# UART.net
KiCad netlist of a schematic drawn in Altium Designer
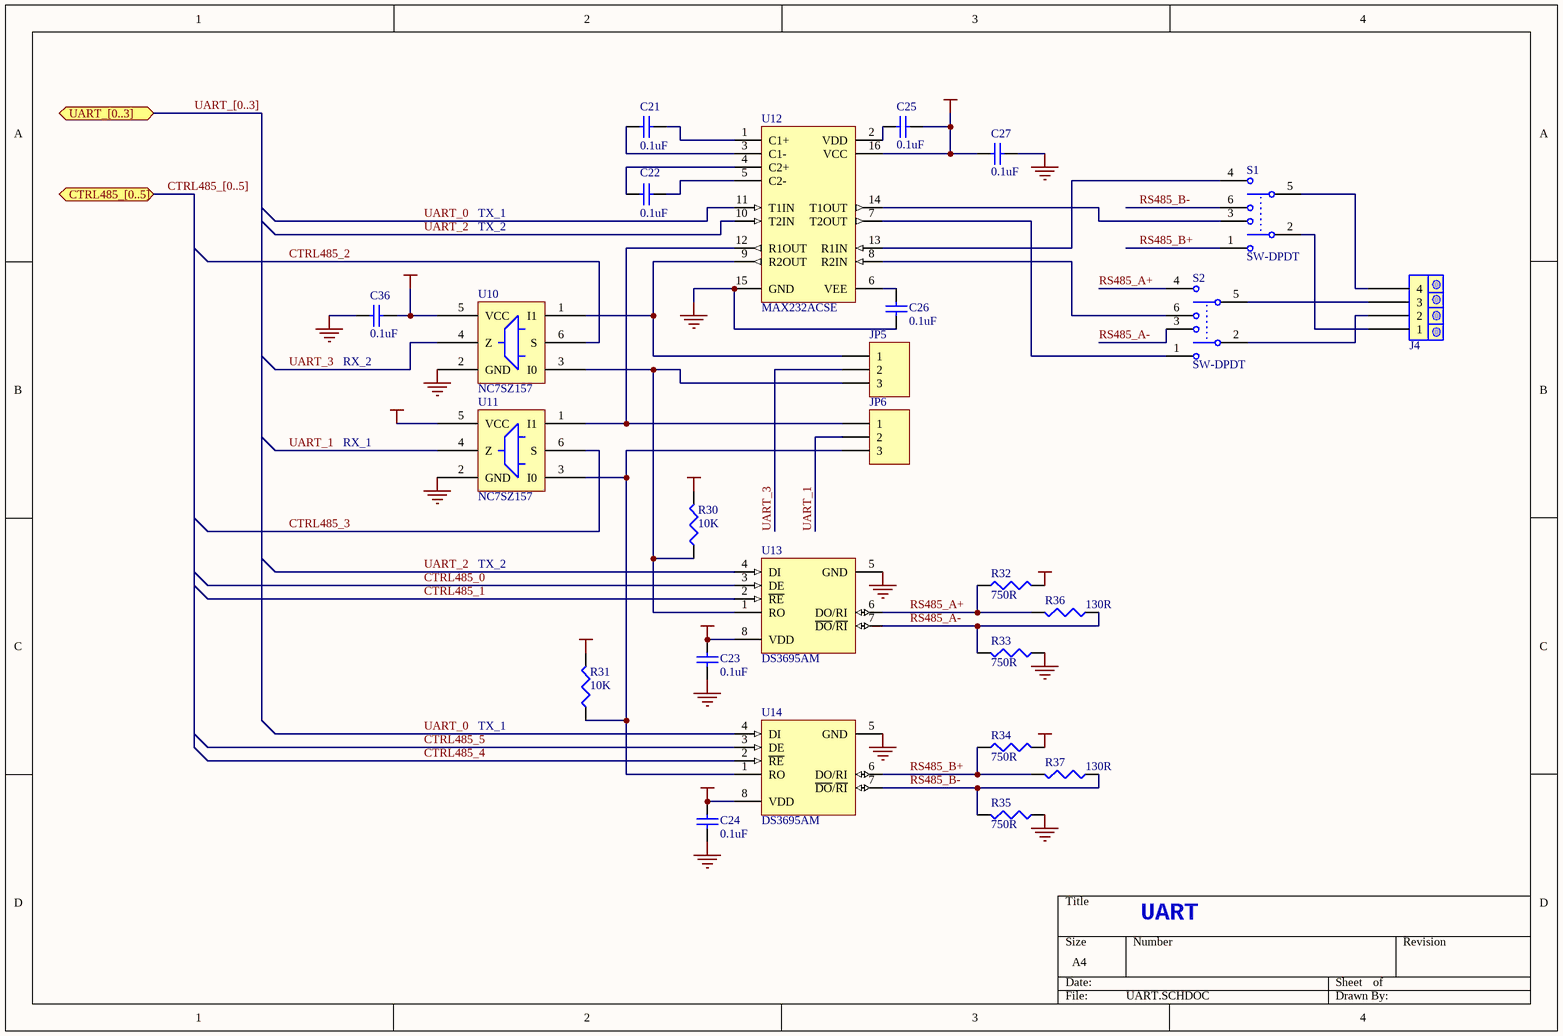
[diagram p0: UART.SCHDOC]

(export (version "E")
  (design (tool "Eeschema 10.0.6"))
  (components
    (comp (ref "C21")
      (value "0.1uF")
      (footprint "_0805")
      (description "Capacitor (Semiconductor SIM Model)")
      (fields (field (name "Comment") "Cap Semi") (field (name "PUBLISHER") "Altium Limited"))
      (libsource (lib "Miscellaneous Devices") (part "Cap Semi"))
    )
    (comp (ref "C22")
      (value "0.1uF")
      (footprint "_0805")
      (description "Capacitor (Semiconductor SIM Model)")
      (fields (field (name "Comment") "Cap Semi") (field (name "PUBLISHER") "Altium Limited"))
      (libsource (lib "Miscellaneous Devices") (part "Cap Semi"))
    )
    (comp (ref "C23")
      (value "0.1uF")
      (footprint "_0805")
      (description "Capacitor (Semiconductor SIM Model)")
      (fields (field (name "Comment") "Cap Semi") (field (name "PUBLISHER") "Altium Limited"))
      (libsource (lib "Miscellaneous Devices") (part "Cap Semi"))
    )
    (comp (ref "C24")
      (value "0.1uF")
      (footprint "_0805")
      (description "Capacitor (Semiconductor SIM Model)")
      (fields (field (name "Comment") "Cap Semi") (field (name "PUBLISHER") "Altium Limited"))
      (libsource (lib "Miscellaneous Devices") (part "Cap Semi"))
    )
    (comp (ref "C25")
      (value "0.1uF")
      (footprint "_0805")
      (description "Capacitor (Semiconductor SIM Model)")
      (fields (field (name "Comment") "Cap Semi") (field (name "PUBLISHER") "Altium Limited"))
      (libsource (lib "Miscellaneous Devices") (part "Cap Semi"))
    )
    (comp (ref "C26")
      (value "0.1uF")
      (footprint "_0805")
      (description "Capacitor (Semiconductor SIM Model)")
      (fields (field (name "Comment") "Cap Semi") (field (name "PUBLISHER") "Altium Limited"))
      (libsource (lib "Miscellaneous Devices") (part "Cap Semi"))
    )
    (comp (ref "C27")
      (value "0.1uF")
      (footprint "_0805")
      (description "Capacitor (Semiconductor SIM Model)")
      (fields (field (name "Comment") "Cap Semi") (field (name "PUBLISHER") "Altium Limited"))
      (libsource (lib "Miscellaneous Devices") (part "Cap Semi"))
    )
    (comp (ref "C36")
      (value "0.1uF")
      (footprint "_0805")
      (description "Capacitor (Semiconductor SIM Model)")
      (fields (field (name "Comment") "Cap Semi") (field (name "PUBLISHER") "Altium Limited"))
      (libsource (lib "Miscellaneous Devices") (part "Cap Semi"))
    )
    (comp (ref "J4")
      (value "BORNERA_X4")
      (footprint "BORNERA_X4")
      (libsource (lib "Custom") (part "BORNERA_X4"))
    )
    (comp (ref "JP5")
      (value "Header 3")
      (footprint "HDR1X3")
      (description "Header, 3-Pin")
      (fields (field (name "PUBLISHER") "Altium Limited"))
      (libsource (lib "Miscellaneous Connectors") (part "Header 3"))
    )
    (comp (ref "JP6")
      (value "Header 3")
      (footprint "HDR1X3")
      (description "Header, 3-Pin")
      (fields (field (name "PUBLISHER") "Altium Limited"))
      (libsource (lib "Miscellaneous Connectors") (part "Header 3"))
    )
    (comp (ref "R30")
      (value "10K")
      (footprint "_0805")
      (description "Resistor")
      (fields (field (name "Comment") "Res3") (field (name "PUBLISHER") "Altium Limited"))
      (libsource (lib "Miscellaneous Devices") (part "Res3"))
    )
    (comp (ref "R31")
      (value "10K")
      (footprint "_0805")
      (description "Resistor")
      (fields (field (name "Comment") "Res3") (field (name "PUBLISHER") "Altium Limited"))
      (libsource (lib "Miscellaneous Devices") (part "Res3"))
    )
    (comp (ref "R32")
      (value "750R")
      (footprint "_1206")
      (description "Resistor")
      (fields (field (name "Comment") "Res3") (field (name "PUBLISHER") "Altium Limited"))
      (libsource (lib "Miscellaneous Devices") (part "Res3"))
    )
    (comp (ref "R33")
      (value "750R")
      (footprint "_1206")
      (description "Resistor")
      (fields (field (name "Comment") "Res3") (field (name "PUBLISHER") "Altium Limited"))
      (libsource (lib "Miscellaneous Devices") (part "Res3"))
    )
    (comp (ref "R34")
      (value "750R")
      (footprint "_1206")
      (description "Resistor")
      (fields (field (name "Comment") "Res3") (field (name "PUBLISHER") "Altium Limited"))
      (libsource (lib "Miscellaneous Devices") (part "Res3"))
    )
    (comp (ref "R35")
      (value "750R")
      (footprint "_1206")
      (description "Resistor")
      (fields (field (name "Comment") "Res3") (field (name "PUBLISHER") "Altium Limited"))
      (libsource (lib "Miscellaneous Devices") (part "Res3"))
    )
    (comp (ref "R36")
      (value "130R")
      (footprint "_1206")
      (description "Resistor")
      (fields (field (name "Comment") "Res3") (field (name "PUBLISHER") "Altium Limited"))
      (libsource (lib "Miscellaneous Devices") (part "Res3"))
    )
    (comp (ref "R37")
      (value "130R")
      (footprint "_1206")
      (description "Resistor")
      (fields (field (name "Comment") "Res3") (field (name "PUBLISHER") "Altium Limited"))
      (libsource (lib "Miscellaneous Devices") (part "Res3"))
    )
    (comp (ref "S1")
      (value "SW-DPDT")
      (footprint "Switch_EG2207")
      (description "Double-Pole, Double-Throw Switch")
      (fields (field (name "PUBLISHER") "Altium Limited"))
      (libsource (lib "Miscellaneous Devices") (part "SW-DPDT"))
    )
    (comp (ref "S2")
      (value "SW-DPDT")
      (footprint "Switch_EG2207")
      (description "Double-Pole, Double-Throw Switch")
      (fields (field (name "PUBLISHER") "Altium Limited"))
      (libsource (lib "Miscellaneous Devices") (part "SW-DPDT"))
    )
    (comp (ref "U10")
      (value "NC7SZ157")
      (footprint "SO-G6/Z2.8")
      (description "Tiny Logic 2-Input Non-Inverter Mux")
      (libsource (lib "Custom") (part "NC7SZ157"))
    )
    (comp (ref "U11")
      (value "NC7SZ157")
      (footprint "SO-G6/Z2.8")
      (description "Tiny Logic 2-Input Non-Inverter Mux")
      (libsource (lib "Custom") (part "NC7SZ157"))
    )
    (comp (ref "U12")
      (value "MAX232ACSE")
      (footprint "NSO16")
      (description "+5V Powered, Multi-Channel RS-232 Driver/Receiver")
      (fields (field (name "PUBLISHER") "Altium Limited"))
      (libsource (lib "Maxim Communication Transceiver") (part "MAX232ACSE"))
    )
    (comp (ref "U13")
      (value "DS3695AM")
      (footprint "M08A")
      (description "Multipoint RS485/RS422 Transceiver")
      (fields (field (name "PUBLISHER") "Altium Limited"))
      (libsource (lib "NSC Interface Line Transceiver") (part "DS3695AM"))
    )
    (comp (ref "U14")
      (value "DS3695AM")
      (footprint "M08A")
      (description "Multipoint RS485/RS422 Transceiver")
      (fields (field (name "PUBLISHER") "Altium Limited"))
      (libsource (lib "NSC Interface Line Transceiver") (part "DS3695AM"))
    )
  )
  (nets
    (net (code "1") (name "/CTRL485_0") (class "Default")
      (node (ref "U13") (pin "3") (pinfunction "DE_3") (pintype "input"))
    )
    (net (code "2") (name "/CTRL485_1") (class "Default")
      (node (ref "U13") (pin "2") (pinfunction "~{RE}_2") (pintype "input"))
    )
    (net (code "3") (name "/CTRL485_2") (class "Default")
      (node (ref "U10") (pin "6") (pinfunction "S_6") (pintype "passive"))
    )
    (net (code "4") (name "/CTRL485_3") (class "Default")
      (node (ref "U11") (pin "6") (pinfunction "S_6") (pintype "passive"))
    )
    (net (code "5") (name "/CTRL485_4") (class "Default")
      (node (ref "U14") (pin "2") (pinfunction "~{RE}_2") (pintype "input"))
    )
    (net (code "6") (name "/CTRL485_5") (class "Default")
      (node (ref "U14") (pin "3") (pinfunction "DE_3") (pintype "input"))
    )
    (net (code "8") (name "/RS485_A+") (class "Default")
      (node (ref "R32") (pin "1") (pinfunction "1_1") (pintype "passive"))
      (node (ref "R36") (pin "2") (pinfunction "2_2") (pintype "passive"))
      (node (ref "S2") (pin "4") (pinfunction "6_4") (pintype "passive"))
      (node (ref "U13") (pin "6") (pinfunction "DO/RI_6") (pintype "bidirectional"))
    )
    (net (code "9") (name "/RS485_A-") (class "Default")
      (node (ref "R33") (pin "2") (pinfunction "2_2") (pintype "passive"))
      (node (ref "R36") (pin "1") (pinfunction "1_1") (pintype "passive"))
      (node (ref "S2") (pin "3") (pinfunction "3_3") (pintype "passive"))
      (node (ref "U13") (pin "7") (pinfunction "~{DO}/~{RI}_7") (pintype "bidirectional"))
    )
    (net (code "10") (name "/RS485_B+") (class "Default")
      (node (ref "R34") (pin "1") (pinfunction "1_1") (pintype "passive"))
      (node (ref "R37") (pin "2") (pinfunction "2_2") (pintype "passive"))
      (node (ref "S1") (pin "1") (pinfunction "2_1") (pintype "passive"))
      (node (ref "U14") (pin "6") (pinfunction "DO/RI_6") (pintype "bidirectional"))
    )
    (net (code "11") (name "/RS485_B-") (class "Default")
      (node (ref "R35") (pin "2") (pinfunction "2_2") (pintype "passive"))
      (node (ref "R37") (pin "1") (pinfunction "1_1") (pintype "passive"))
      (node (ref "S1") (pin "6") (pinfunction "5_6") (pintype "passive"))
      (node (ref "U14") (pin "7") (pinfunction "~{DO}/~{RI}_7") (pintype "bidirectional"))
    )
    (net (code "12") (name "/UART_0") (class "Default")
      (node (ref "U12") (pin "11") (pinfunction "T1IN_11") (pintype "input"))
      (node (ref "U14") (pin "4") (pinfunction "DI_4") (pintype "input"))
    )
    (net (code "13") (name "/UART_1") (class "Default")
      (node (ref "JP6") (pin "2") (pinfunction "2_2") (pintype "passive"))
      (node (ref "U11") (pin "4") (pinfunction "Z_4") (pintype "passive"))
    )
    (net (code "14") (name "/UART_2") (class "Default")
      (node (ref "U12") (pin "10") (pinfunction "T2IN_10") (pintype "input"))
      (node (ref "U13") (pin "4") (pinfunction "DI_4") (pintype "input"))
    )
    (net (code "15") (name "/UART_3") (class "Default")
      (node (ref "JP5") (pin "2") (pinfunction "2_2") (pintype "passive"))
      (node (ref "U10") (pin "4") (pinfunction "Z_4") (pintype "passive"))
    )
    (net (code "17") (name "GND") (class "Default")
      (node (ref "C23") (pin "2") (pinfunction "2_2") (pintype "passive"))
      (node (ref "C24") (pin "2") (pinfunction "2_2") (pintype "passive"))
      (node (ref "C26") (pin "2") (pinfunction "2_2") (pintype "passive"))
      (node (ref "C27") (pin "2") (pinfunction "2_2") (pintype "passive"))
      (node (ref "C36") (pin "1") (pinfunction "1_1") (pintype "passive"))
      (node (ref "R33") (pin "1") (pinfunction "1_1") (pintype "passive"))
      (node (ref "R35") (pin "1") (pinfunction "1_1") (pintype "passive"))
      (node (ref "U10") (pin "2") (pinfunction "GND_2") (pintype "power_in"))
      (node (ref "U11") (pin "2") (pinfunction "GND_2") (pintype "power_in"))
      (node (ref "U12") (pin "15") (pinfunction "GND_15") (pintype "power_in"))
      (node (ref "U13") (pin "5") (pinfunction "GND_5") (pintype "power_in"))
      (node (ref "U14") (pin "5") (pinfunction "GND_5") (pintype "power_in"))
    )
    (net (code "18") (name "Net-(S1-1)") (class "Default")
      (node (ref "J4") (pin "1") (pinfunction "1_1") (pintype "passive"))
      (node (ref "S1") (pin "2") (pinfunction "1_2") (pintype "passive"))
    )
    (net (code "19") (name "Net-(S1-4)") (class "Default")
      (node (ref "J4") (pin "4") (pinfunction "4_4") (pintype "passive"))
      (node (ref "S1") (pin "5") (pinfunction "4_5") (pintype "passive"))
    )
    (net (code "20") (name "Net-(S1-6)") (class "Default")
      (node (ref "S1") (pin "4") (pinfunction "6_4") (pintype "passive"))
      (node (ref "U12") (pin "13") (pinfunction "R1IN_13") (pintype "input"))
    )
    (net (code "21") (name "Net-(S2-1)") (class "Default")
      (node (ref "J4") (pin "2") (pinfunction "2_2") (pintype "passive"))
      (node (ref "S2") (pin "2") (pinfunction "1_2") (pintype "passive"))
    )
    (net (code "22") (name "Net-(S2-2)") (class "Default")
      (node (ref "S2") (pin "1") (pinfunction "2_1") (pintype "passive"))
      (node (ref "U12") (pin "7") (pinfunction "T2OUT_7") (pintype "output"))
    )
    (net (code "23") (name "Net-(S2-4)") (class "Default")
      (node (ref "J4") (pin "3") (pinfunction "3_3") (pintype "passive"))
      (node (ref "S2") (pin "5") (pinfunction "4_5") (pintype "passive"))
    )
    (net (code "24") (name "Net-(S2-5)") (class "Default")
      (node (ref "S2") (pin "6") (pinfunction "5_6") (pintype "passive"))
      (node (ref "U12") (pin "8") (pinfunction "R2IN_8") (pintype "input"))
    )
    (net (code "25") (name "Net-(U10-I0)") (class "Default")
      (node (ref "JP5") (pin "3") (pinfunction "3_3") (pintype "passive"))
      (node (ref "R30") (pin "1") (pinfunction "1_1") (pintype "passive"))
      (node (ref "U10") (pin "3") (pinfunction "I0_3") (pintype "passive"))
      (node (ref "U13") (pin "1") (pinfunction "RO_1") (pintype "tri_state"))
    )
    (net (code "26") (name "Net-(U10-I1)") (class "Default")
      (node (ref "JP5") (pin "1") (pinfunction "1_1") (pintype "passive"))
      (node (ref "U10") (pin "1") (pinfunction "I1_1") (pintype "passive"))
      (node (ref "U12") (pin "9") (pinfunction "R2OUT_9") (pintype "output"))
    )
    (net (code "27") (name "Net-(U11-I0)") (class "Default")
      (node (ref "JP6") (pin "3") (pinfunction "3_3") (pintype "passive"))
      (node (ref "R31") (pin "1") (pinfunction "1_1") (pintype "passive"))
      (node (ref "U11") (pin "3") (pinfunction "I0_3") (pintype "passive"))
      (node (ref "U14") (pin "1") (pinfunction "RO_1") (pintype "tri_state"))
    )
    (net (code "28") (name "Net-(U11-I1)") (class "Default")
      (node (ref "JP6") (pin "1") (pinfunction "1_1") (pintype "passive"))
      (node (ref "U11") (pin "1") (pinfunction "I1_1") (pintype "passive"))
      (node (ref "U12") (pin "12") (pinfunction "R1OUT_12") (pintype "output"))
    )
    (net (code "29") (name "Net-(U12-C1+)") (class "Default")
      (node (ref "C21") (pin "2") (pinfunction "2_2") (pintype "passive"))
      (node (ref "U12") (pin "1") (pinfunction "C1+_1") (pintype "passive"))
    )
    (net (code "30") (name "Net-(U12-C1-)") (class "Default")
      (node (ref "C21") (pin "1") (pinfunction "1_1") (pintype "passive"))
      (node (ref "U12") (pin "3") (pinfunction "C1-_3") (pintype "passive"))
    )
    (net (code "31") (name "Net-(U12-C2+)") (class "Default")
      (node (ref "C22") (pin "1") (pinfunction "1_1") (pintype "passive"))
      (node (ref "U12") (pin "4") (pinfunction "C2+_4") (pintype "passive"))
    )
    (net (code "32") (name "Net-(U12-C2-)") (class "Default")
      (node (ref "C22") (pin "2") (pinfunction "2_2") (pintype "passive"))
      (node (ref "U12") (pin "5") (pinfunction "C2-_5") (pintype "passive"))
    )
    (net (code "33") (name "Net-(U12-T1OUT)") (class "Default")
      (node (ref "S1") (pin "3") (pinfunction "3_3") (pintype "passive"))
      (node (ref "U12") (pin "14") (pinfunction "T1OUT_14") (pintype "output"))
    )
    (net (code "34") (name "Net-(U12-VDD)") (class "Default")
      (node (ref "C25") (pin "2") (pinfunction "2_2") (pintype "passive"))
      (node (ref "U12") (pin "2") (pinfunction "VDD_2") (pintype "power_in"))
    )
    (net (code "35") (name "Net-(U12-VEE)") (class "Default")
      (node (ref "C26") (pin "1") (pinfunction "1_1") (pintype "passive"))
      (node (ref "U12") (pin "6") (pinfunction "VEE_6") (pintype "power_in"))
    )
    (net (code "36") (name "VCC_3V") (class "Default")
      (node (ref "C36") (pin "2") (pinfunction "2_2") (pintype "passive"))
      (node (ref "U10") (pin "5") (pinfunction "VCC_5") (pintype "power_in"))
      (node (ref "U11") (pin "5") (pinfunction "VCC_5") (pintype "power_in"))
    )
    (net (code "37") (name "VCC_5V") (class "Default")
      (node (ref "C23") (pin "1") (pinfunction "1_1") (pintype "passive"))
      (node (ref "C24") (pin "1") (pinfunction "1_1") (pintype "passive"))
      (node (ref "C25") (pin "1") (pinfunction "1_1") (pintype "passive"))
      (node (ref "C27") (pin "1") (pinfunction "1_1") (pintype "passive"))
      (node (ref "R30") (pin "2") (pinfunction "2_2") (pintype "passive"))
      (node (ref "R31") (pin "2") (pinfunction "2_2") (pintype "passive"))
      (node (ref "R32") (pin "2") (pinfunction "2_2") (pintype "passive"))
      (node (ref "R34") (pin "2") (pinfunction "2_2") (pintype "passive"))
      (node (ref "U12") (pin "16") (pinfunction "VCC_16") (pintype "power_in"))
      (node (ref "U13") (pin "8") (pinfunction "VDD_8") (pintype "power_in"))
      (node (ref "U14") (pin "8") (pinfunction "VDD_8") (pintype "power_in"))
    )
  )
)
